# Placa_de_ense_anza.net
KiCad netlist of a schematic drawn in EasyEDA
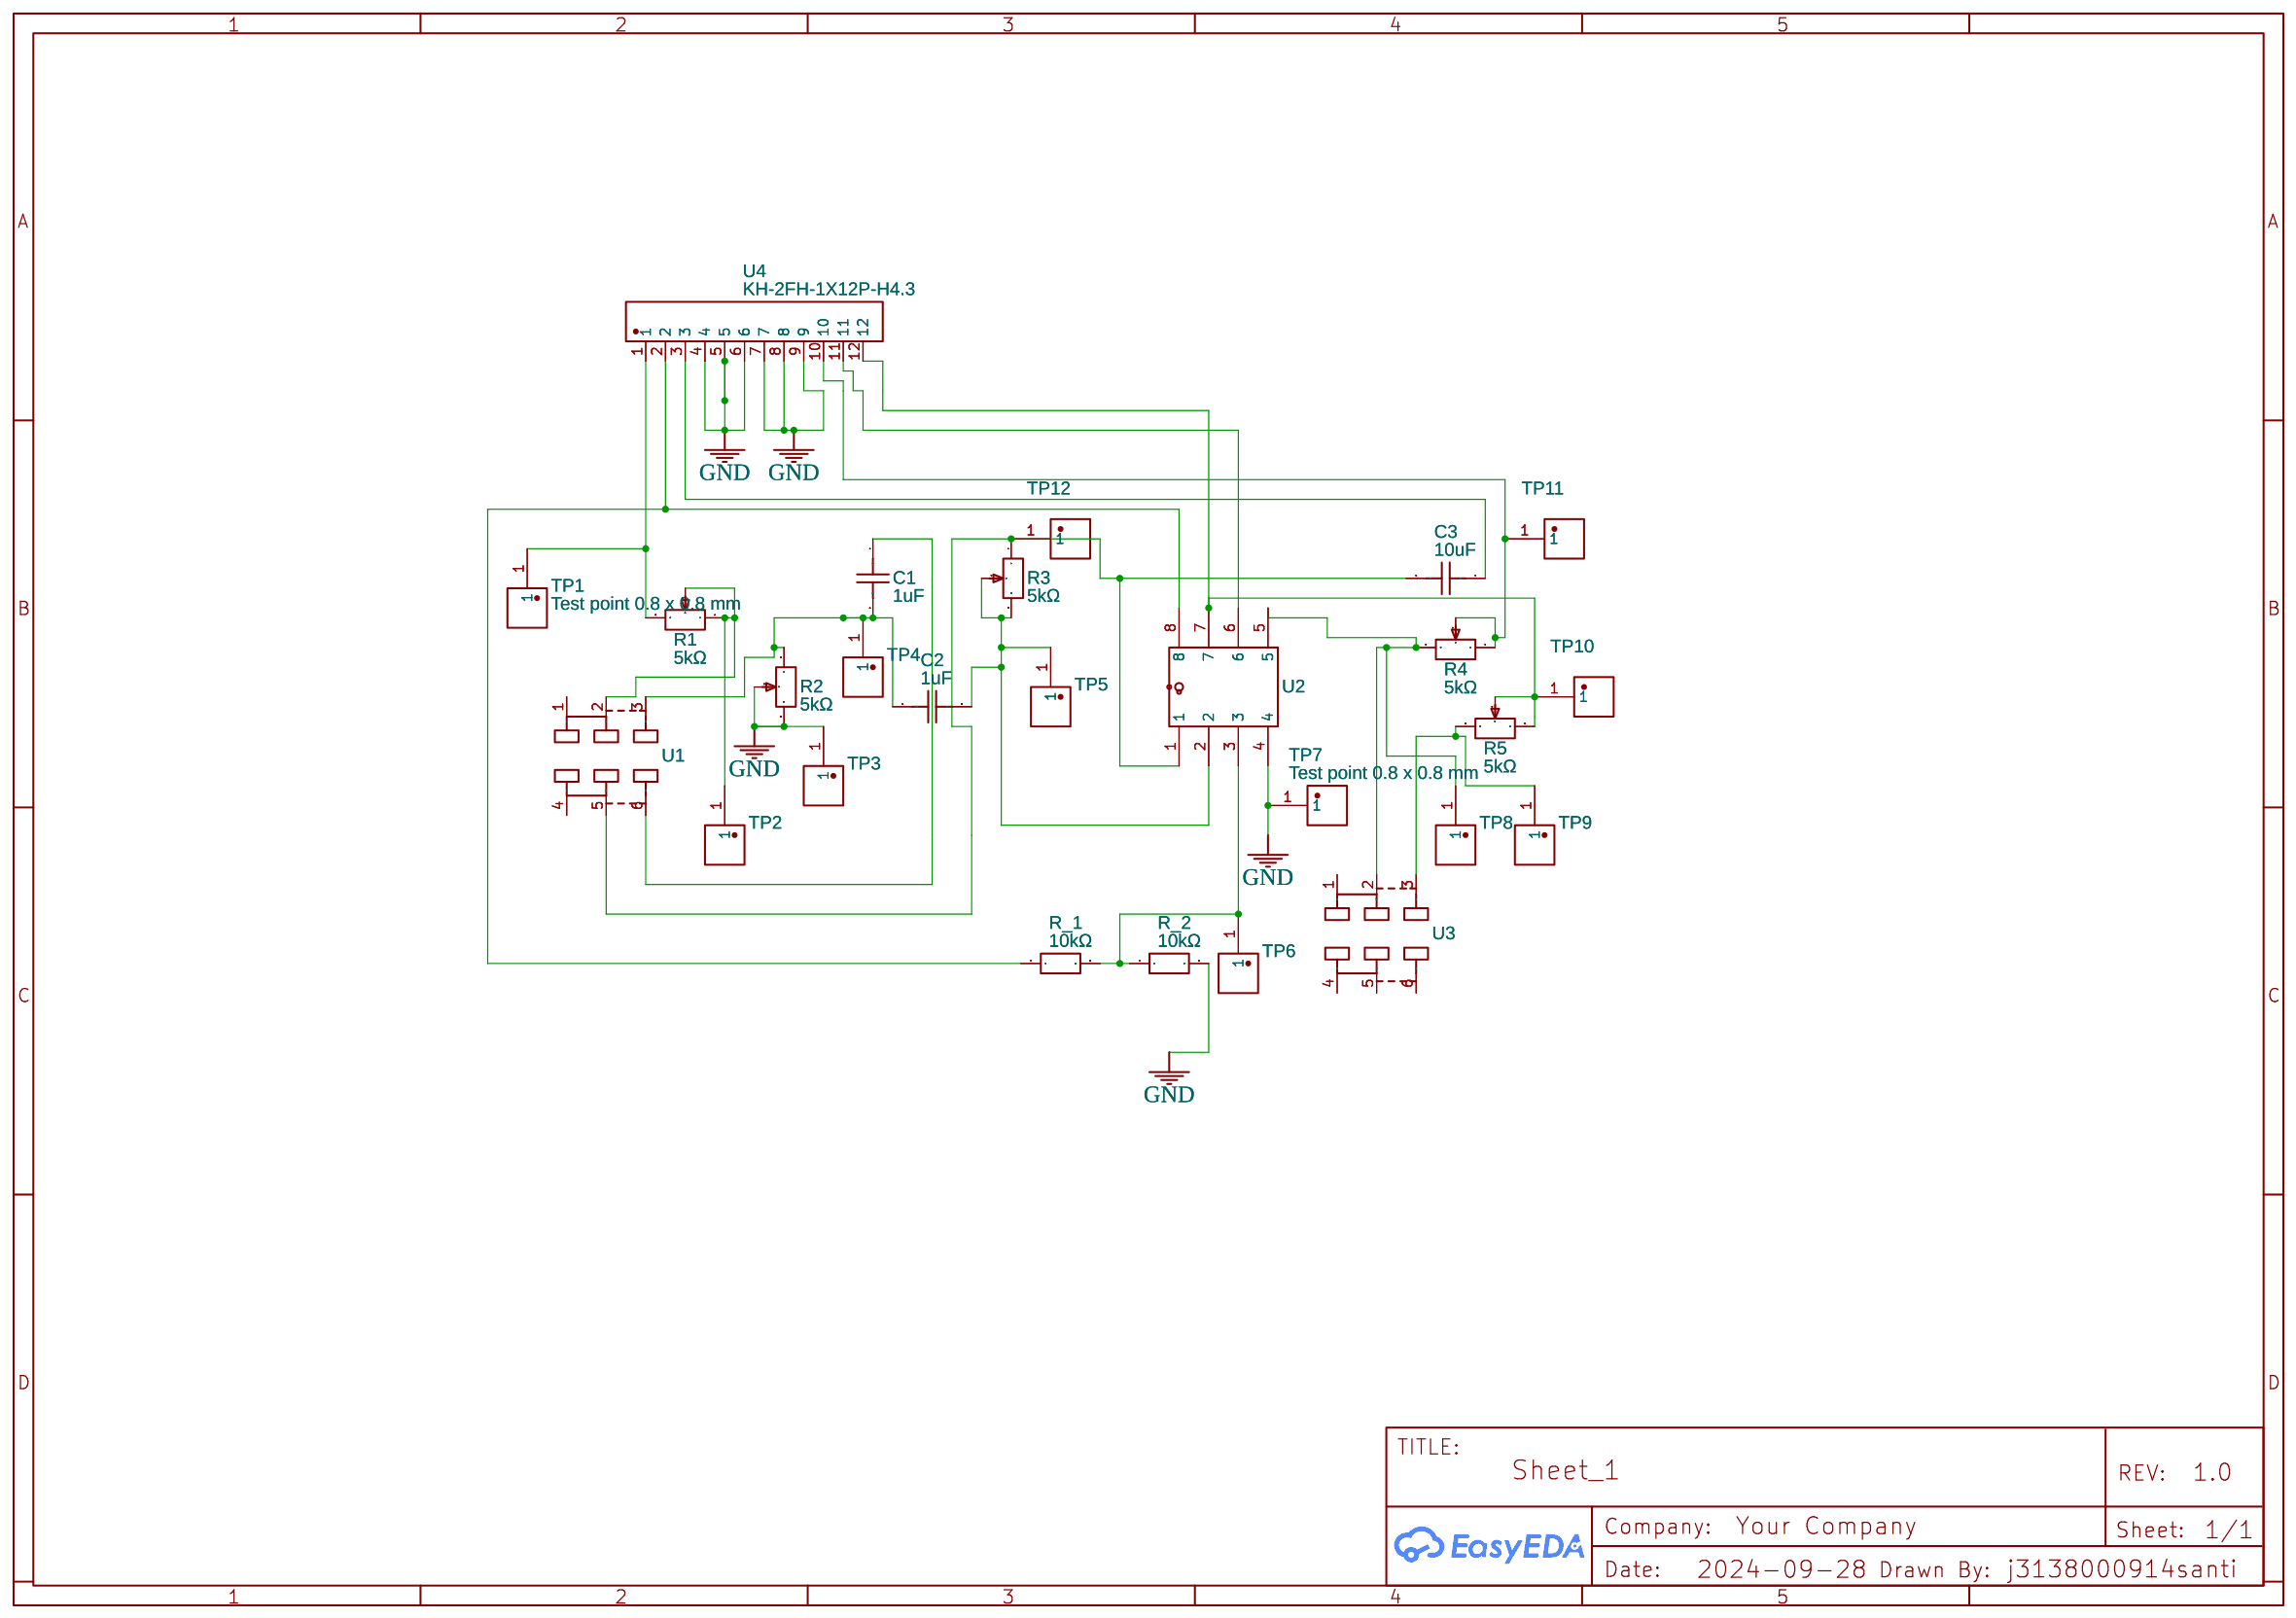
[diagram p0: schematic sheet]

(export (version "E")
  (design (tool "Eeschema 10.0.6"))
  (components
    (comp (ref "C1")
      (value "1uF")
      (fields
        (field (name "Manufacturer Part") "CT41G-0805-2X1-50V-1μF-K(N)")
        (field (name "Manufacturer") "TORCH(火炬)")
      )
      (libsource (lib "") (part "CT41G-0805-2X1-50V-1μF-K(N)"))
    )
    (comp (ref "C2")
      (value "1uF")
      (fields
        (field (name "Manufacturer Part") "CT41G-0805-2X1-50V-1μF-K(N)")
        (field (name "Manufacturer") "TORCH(火炬)")
      )
      (libsource (lib "") (part "CT41G-0805-2X1-50V-1μF-K(N)_1"))
    )
    (comp (ref "C3")
      (value "10uF")
      (fields
        (field (name "Manufacturer Part") "C0805X5R106K160NT")
        (field (name "Manufacturer") "SANYEAR(叁叶源)")
      )
      (libsource (lib "") (part "C0805X5R106K160NT"))
    )
    (comp (ref "R1")
      (value "5kΩ")
      (fields (field (name "Manufacturer Part") "3362P-1-502LF") (field (name "Manufacturer") "BOURNS"))
      (libsource (lib "") (part "3362P-1-502LF"))
    )
    (comp (ref "R2")
      (value "5kΩ")
      (fields (field (name "Manufacturer Part") "3362P-1-502LF") (field (name "Manufacturer") "BOURNS"))
      (libsource (lib "") (part "3362P-1-502LF_1"))
    )
    (comp (ref "R3")
      (value "5kΩ")
      (fields (field (name "Manufacturer Part") "3362P-1-502LF") (field (name "Manufacturer") "BOURNS"))
      (libsource (lib "") (part "3362P-1-502LF_1"))
    )
    (comp (ref "R4")
      (value "5kΩ")
      (fields (field (name "Manufacturer Part") "3362P-1-502LF") (field (name "Manufacturer") "BOURNS"))
      (libsource (lib "") (part "3362P-1-502LF"))
    )
    (comp (ref "R5")
      (value "5kΩ")
      (fields (field (name "Manufacturer Part") "3362P-1-502LF") (field (name "Manufacturer") "BOURNS"))
      (libsource (lib "") (part "3362P-1-502LF"))
    )
    (comp (ref "R_1")
      (value "10kΩ")
      (fields (field (name "Manufacturer Part") "CR0805-8W-103JT") (field (name "Manufacturer") "Venkel"))
      (libsource (lib "") (part "CR0805-8W-103JT"))
    )
    (comp (ref "R_2")
      (value "10kΩ")
      (fields (field (name "Manufacturer Part") "CR0805-8W-103JT") (field (name "Manufacturer") "Venkel"))
      (libsource (lib "") (part "CR0805-8W-103JT"))
    )
    (comp (ref "TP1") (value "Test point 0.8 x 0.8 mm") (libsource (lib "") (part "Test point 0.8 x 0.8 mm")))
    (comp (ref "TP2") (value "Test point 0.8 x 0.8 mm") (libsource (lib "") (part "Test point 0.8 x 0.8 mm")))
    (comp (ref "TP3") (value "Test point 0.8 x 0.8 mm") (libsource (lib "") (part "Test point 0.8 x 0.8 mm")))
    (comp (ref "TP4") (value "Test point 0.8 x 0.8 mm") (libsource (lib "") (part "Test point 0.8 x 0.8 mm")))
    (comp (ref "TP5") (value "Test point 0.8 x 0.8 mm") (libsource (lib "") (part "Test point 0.8 x 0.8 mm")))
    (comp (ref "TP6") (value "Test point 0.8 x 0.8 mm") (libsource (lib "") (part "Test point 0.8 x 0.8 mm")))
    (comp (ref "TP7")
      (value "Test point 0.8 x 0.8 mm")
      (libsource (lib "") (part "Test point 0.8 x 0.8 mm_1"))
    )
    (comp (ref "TP8") (value "Test point 0.8 x 0.8 mm") (libsource (lib "") (part "Test point 0.8 x 0.8 mm")))
    (comp (ref "TP9") (value "Test point 0.8 x 0.8 mm") (libsource (lib "") (part "Test point 0.8 x 0.8 mm")))
    (comp (ref "TP10")
      (value "Test point 0.8 x 0.8 mm")
      (libsource (lib "") (part "Test point 0.8 x 0.8 mm_1"))
    )
    (comp (ref "TP11")
      (value "Test point 0.8 x 0.8 mm")
      (libsource (lib "") (part "Test point 0.8 x 0.8 mm_1"))
    )
    (comp (ref "TP12")
      (value "Test point 0.8 x 0.8 mm")
      (libsource (lib "") (part "Test point 0.8 x 0.8 mm_1"))
    )
    (comp (ref "U1")
      (value "HX MSS22D18G2")
      (fields (field (name "Manufacturer") "hanxia(韩下)"))
      (libsource (lib "") (part "HX MSS22D18G2"))
    )
    (comp (ref "U2")
      (value "8 Pin DIP Socket")
      (fields (field (name "Manufacturer Part") "New SchematicLib"))
      (libsource (lib "") (part "8 Pin DIP Socket"))
    )
    (comp (ref "U3")
      (value "HX MSS22D18G2")
      (fields (field (name "Manufacturer") "hanxia(韩下)"))
      (libsource (lib "") (part "HX MSS22D18G2"))
    )
    (comp (ref "U4")
      (value "KH-2FH-1X12P-H4.3")
      (fields (field (name "Manufacturer") "kinghelm(金航标)"))
      (libsource (lib "") (part "KH-2FH-1X12P-H4.3"))
    )
  )
  (nets
    (net (code "1") (name "GND") (class "Default")
      (node (ref "R2") (pin "2") (pinfunction "2_2") (pintype "input"))
      (node (ref "R2") (pin "3") (pinfunction "3_3") (pintype "input"))
      (node (ref "R_2") (pin "2") (pinfunction "2_2") (pintype "unspecified"))
      (node (ref "TP3") (pin "1") (pinfunction "1_1") (pintype "unspecified"))
      (node (ref "TP7") (pin "1") (pinfunction "1_1") (pintype "unspecified"))
      (node (ref "U2") (pin "4") (pinfunction "4_4") (pintype "unspecified"))
      (node (ref "U4") (pin "4") (pinfunction "4_4") (pintype "unspecified"))
      (node (ref "U4") (pin "5") (pinfunction "5_5") (pintype "unspecified"))
      (node (ref "U4") (pin "6") (pinfunction "6_6") (pintype "unspecified"))
      (node (ref "U4") (pin "7") (pinfunction "7_7") (pintype "unspecified"))
      (node (ref "U4") (pin "8") (pinfunction "8_8") (pintype "unspecified"))
      (node (ref "U4") (pin "9") (pinfunction "9_9") (pintype "unspecified"))
    )
    (net (code "2") (name "Net-(C1-Pad1)") (class "Default")
      (node (ref "C1") (pin "1") (pinfunction "1_1") (pintype "unspecified"))
      (node (ref "U1") (pin "6") (pinfunction "6_6") (pintype "unspecified"))
    )
    (net (code "3") (name "Net-(C1-Pad2)") (class "Default")
      (node (ref "C1") (pin "2") (pinfunction "2_2") (pintype "unspecified"))
      (node (ref "C2") (pin "1") (pinfunction "1_1") (pintype "unspecified"))
      (node (ref "R2") (pin "1") (pinfunction "1_1") (pintype "input"))
      (node (ref "TP4") (pin "1") (pinfunction "1_1") (pintype "unspecified"))
      (node (ref "U1") (pin "3") (pinfunction "3_3") (pintype "unspecified"))
    )
    (net (code "4") (name "Net-(C2-Pad2)") (class "Default")
      (node (ref "C2") (pin "2") (pinfunction "2_2") (pintype "unspecified"))
      (node (ref "R3") (pin "2") (pinfunction "2_2") (pintype "input"))
      (node (ref "R3") (pin "3") (pinfunction "3_3") (pintype "input"))
      (node (ref "TP5") (pin "1") (pinfunction "1_1") (pintype "unspecified"))
      (node (ref "U2") (pin "2") (pinfunction "2_2") (pintype "unspecified"))
    )
    (net (code "5") (name "Net-(C3-Pad1)") (class "Default")
      (node (ref "C3") (pin "1") (pinfunction "1_1") (pintype "unspecified"))
      (node (ref "U4") (pin "3") (pinfunction "3_3") (pintype "unspecified"))
    )
    (net (code "6") (name "Net-(C3-Pad2)") (class "Default")
      (node (ref "C3") (pin "2") (pinfunction "2_2") (pintype "unspecified"))
      (node (ref "R3") (pin "1") (pinfunction "1_1") (pintype "input"))
      (node (ref "TP12") (pin "1") (pinfunction "1_1") (pintype "unspecified"))
      (node (ref "U1") (pin "5") (pinfunction "5_5") (pintype "unspecified"))
      (node (ref "U2") (pin "1") (pinfunction "1_1") (pintype "unspecified"))
    )
    (net (code "7") (name "Net-(R1-Pad1)") (class "Default")
      (node (ref "R1") (pin "1") (pinfunction "1_1") (pintype "input"))
      (node (ref "R1") (pin "2") (pinfunction "2_2") (pintype "input"))
      (node (ref "TP2") (pin "1") (pinfunction "1_1") (pintype "unspecified"))
      (node (ref "U1") (pin "2") (pinfunction "2_2") (pintype "unspecified"))
    )
    (net (code "8") (name "Net-(R1-Pad3)") (class "Default")
      (node (ref "R1") (pin "3") (pinfunction "3_3") (pintype "input"))
      (node (ref "TP1") (pin "1") (pinfunction "1_1") (pintype "unspecified"))
      (node (ref "U4") (pin "1") (pinfunction "1_1") (pintype "unspecified"))
    )
    (net (code "9") (name "Net-(R4-Pad1)") (class "Default")
      (node (ref "R4") (pin "1") (pinfunction "1_1") (pintype "input"))
      (node (ref "R4") (pin "2") (pinfunction "2_2") (pintype "input"))
      (node (ref "TP11") (pin "1") (pinfunction "1_1") (pintype "unspecified"))
      (node (ref "U4") (pin "10") (pinfunction "10_10") (pintype "unspecified"))
    )
    (net (code "10") (name "Net-(R4-Pad3)") (class "Default")
      (node (ref "R4") (pin "3") (pinfunction "3_3") (pintype "input"))
      (node (ref "TP8") (pin "1") (pinfunction "1_1") (pintype "unspecified"))
      (node (ref "U2") (pin "5") (pinfunction "5_5") (pintype "unspecified"))
      (node (ref "U3") (pin "2") (pinfunction "2_2") (pintype "unspecified"))
    )
    (net (code "11") (name "Net-(R5-Pad1)") (class "Default")
      (node (ref "R5") (pin "1") (pinfunction "1_1") (pintype "input"))
      (node (ref "R5") (pin "2") (pinfunction "2_2") (pintype "input"))
      (node (ref "TP10") (pin "1") (pinfunction "1_1") (pintype "unspecified"))
      (node (ref "U2") (pin "7") (pinfunction "7_7") (pintype "unspecified"))
      (node (ref "U4") (pin "12") (pinfunction "12_12") (pintype "unspecified"))
    )
    (net (code "12") (name "Net-(R5-Pad3)") (class "Default")
      (node (ref "R5") (pin "3") (pinfunction "3_3") (pintype "input"))
      (node (ref "TP9") (pin "1") (pinfunction "1_1") (pintype "unspecified"))
      (node (ref "U3") (pin "3") (pinfunction "3_3") (pintype "unspecified"))
    )
    (net (code "13") (name "Net-(R_1-Pad1)") (class "Default")
      (node (ref "R_1") (pin "1") (pinfunction "1_1") (pintype "unspecified"))
      (node (ref "U2") (pin "8") (pinfunction "8_8") (pintype "unspecified"))
      (node (ref "U4") (pin "2") (pinfunction "2_2") (pintype "unspecified"))
    )
    (net (code "14") (name "Net-(R_1-Pad2)") (class "Default")
      (node (ref "R_1") (pin "2") (pinfunction "2_2") (pintype "unspecified"))
      (node (ref "R_2") (pin "1") (pinfunction "1_1") (pintype "unspecified"))
      (node (ref "TP6") (pin "1") (pinfunction "1_1") (pintype "unspecified"))
      (node (ref "U2") (pin "3") (pinfunction "3_3") (pintype "unspecified"))
    )
    (net (code "15") (name "Net-(U2-Pad6)") (class "Default")
      (node (ref "U2") (pin "6") (pinfunction "6_6") (pintype "unspecified"))
      (node (ref "U4") (pin "11") (pinfunction "11_11") (pintype "unspecified"))
    )
    (net (code "16") (name "unconnected-(U1-Pad1)") (class "Default")
      (node (ref "U1") (pin "1") (pinfunction "1_1") (pintype "unspecified"))
    )
    (net (code "17") (name "unconnected-(U1-Pad4)") (class "Default")
      (node (ref "U1") (pin "4") (pinfunction "4_4") (pintype "unspecified"))
    )
    (net (code "18") (name "unconnected-(U3-Pad1)") (class "Default")
      (node (ref "U3") (pin "1") (pinfunction "1_1") (pintype "unspecified"))
    )
    (net (code "19") (name "unconnected-(U3-Pad4)") (class "Default")
      (node (ref "U3") (pin "4") (pinfunction "4_4") (pintype "unspecified"))
    )
    (net (code "20") (name "unconnected-(U3-Pad5)") (class "Default")
      (node (ref "U3") (pin "5") (pinfunction "5_5") (pintype "unspecified"))
    )
    (net (code "21") (name "unconnected-(U3-Pad6)") (class "Default")
      (node (ref "U3") (pin "6") (pinfunction "6_6") (pintype "unspecified"))
    )
  )
)
